# facetHound_inputs_mast_v13.net
KiCad netlist of a schematic drawn in EAGLE
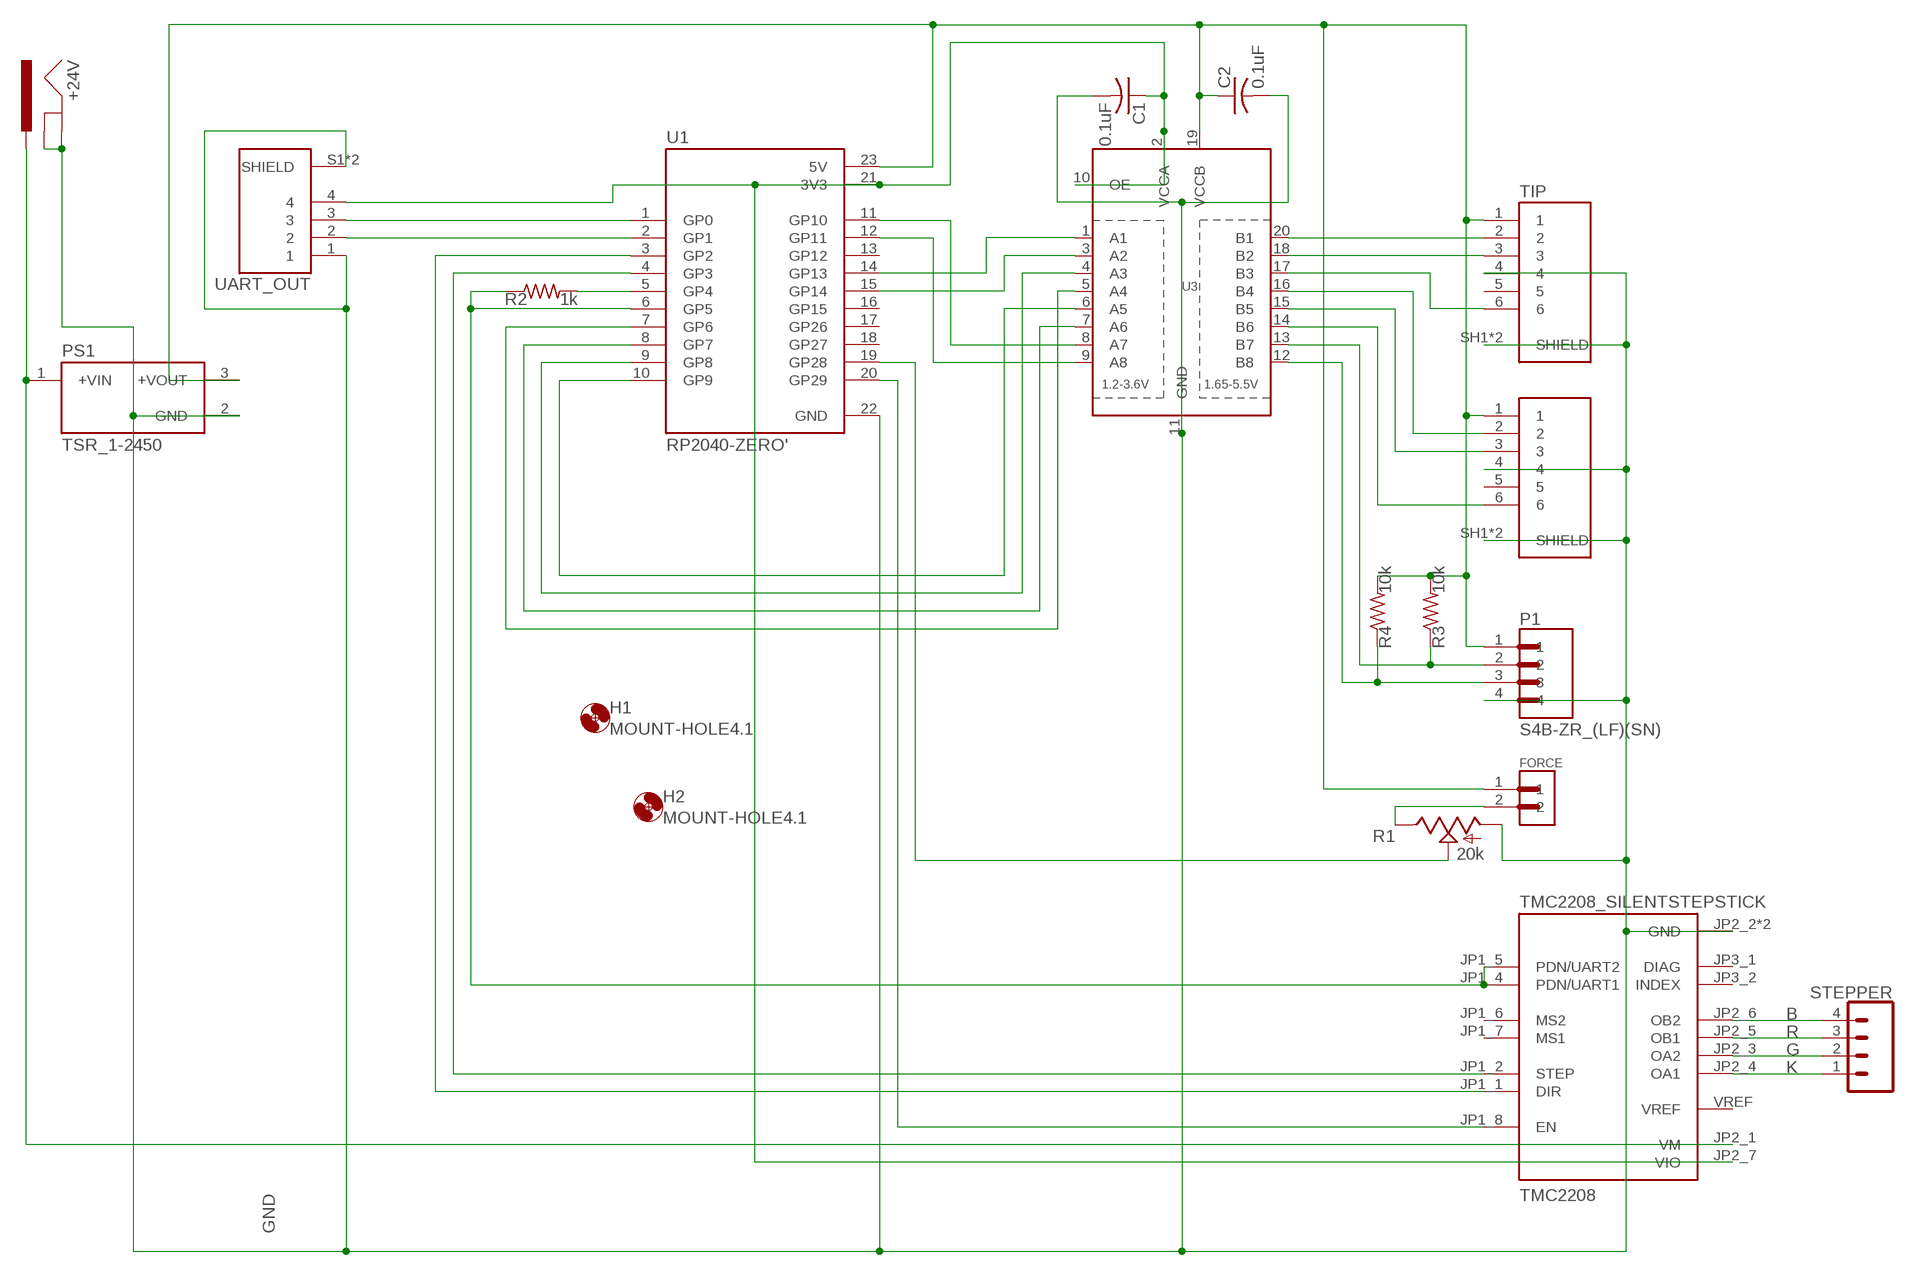
[diagram p0: schematic, sheet 1]

(export (version "E")
  (design (tool "Eeschema 10.0.6"))
  (components
    (comp (ref "+24V")
      (value "POWER_JACKPOWER_JACK_SLOT")
      (footprint "eagle-import:POWER_JACK_PTH_SLOT")
      (libsource (lib "eagle-import") (part "POWER_JACKPOWER_JACK_SLOT"))
    )
    (comp (ref "C1")
      (value "0.1uF")
      (footprint "eagle-import:C1206")
      (libsource (lib "eagle-import") (part "C-USC1206"))
    )
    (comp (ref "C2")
      (value "0.1uF")
      (footprint "eagle-import:C1206")
      (libsource (lib "eagle-import") (part "C-USC1206"))
    )
    (comp (ref "FORCE")
      (value "S2B-ZR-SM4A-TF")
      (footprint "eagle-import:JST_S2B-ZR-SM4A-TF")
      (fields (field (name "MF") "JST Sales"))
      (libsource (lib "eagle-import") (part "S2B-ZR-SM4A-TF"))
    )
    (comp (ref "H1")
      (value "MOUNT-HOLE4.1")
      (footprint "eagle-import:4,1")
      (libsource (lib "eagle-import") (part "MOUNT-HOLE4.1"))
    )
    (comp (ref "H2")
      (value "MOUNT-HOLE4.1")
      (footprint "eagle-import:4,1")
      (libsource (lib "eagle-import") (part "MOUNT-HOLE4.1"))
    )
    (comp (ref "P1")
      (value "S4B-ZR_(LF)(SN)")
      (footprint "eagle-import:JST_S4B-ZR(LF)(SN)")
      (fields (field (name "MF") "JST Sales") (field (name "MP") "S4B-ZR (LF)(SN)"))
      (libsource (lib "eagle-import") (part "S4B-ZR_(LF)(SN)"))
    )
    (comp (ref "PS1")
      (value "TSR_1-2450")
      (footprint "eagle-import:CONV_TSR_1-2450")
      (fields (field (name "MANUFACTURER") "Traco Power"))
      (libsource (lib "eagle-import") (part "TSR_1-2450"))
    )
    (comp (ref "R1")
      (value "20k")
      (footprint "eagle-import:RJ9W")
      (libsource (lib "eagle-import") (part "TRIM_US-RJ9W"))
    )
    (comp (ref "R2")
      (value "1k")
      (footprint "eagle-import:R1206")
      (libsource (lib "eagle-import") (part "R-US_R1206"))
    )
    (comp (ref "R3")
      (value "10k")
      (footprint "eagle-import:R1206")
      (libsource (lib "eagle-import") (part "R-US_R1206"))
    )
    (comp (ref "R4")
      (value "10k")
      (footprint "eagle-import:R1206")
      (libsource (lib "eagle-import") (part "R-US_R1206"))
    )
    (comp (ref "STEPPER")
      (value "CONN_04JST-PTH")
      (footprint "eagle-import:JST-4-PTH")
      (libsource (lib "eagle-import") (part "CONN_04JST-PTH"))
    )
    (comp (ref "TILT")
      (value "S6B-ZR-SM4A-TF(LF)(SN)")
      (footprint "eagle-import:JST_S6B-ZR-SM4A-TF(LF)(SN)")
      (fields (field (name "MF") "JST Sales America Inc."))
      (libsource (lib "eagle-import") (part "S6B-ZR-SM4A-TF(LF)(SN)"))
    )
    (comp (ref "TIP")
      (value "S6B-ZR-SM4A-TF(LF)(SN)")
      (footprint "eagle-import:JST_S6B-ZR-SM4A-TF(LF)(SN)")
      (fields (field (name "MF") "JST Sales America Inc."))
      (libsource (lib "eagle-import") (part "S6B-ZR-SM4A-TF(LF)(SN)"))
    )
    (comp (ref "TMC2208")
      (value "TMC2208_SILENTSTEPSTICK")
      (footprint "eagle-import:MODULE_TMC2208_SILENTSTEPSTICK")
      (fields (field (name "MF") "Trinamic Motion") (field (name "MP") "TMC2208 SILENTSTEPSTICK"))
      (libsource (lib "eagle-import") (part "TMC2208_SILENTSTEPSTICK"))
    )
    (comp (ref "U1")
      (value "RP2040-ZERO'")
      (footprint "eagle-import:MODULE_RP2040-ZERO")
      (fields (field (name "MF") "Waveshare Electronics") (field (name "MP") "RP2040-ZERO"))
      (libsource (lib "eagle-import") (part "RP2040-ZERO'"))
    )
    (comp (ref "U3")
      (value "TXB0108PWR")
      (footprint "eagle-import:TSSOP20")
      (libsource (lib "eagle-import") (part "TXB0108PWR"))
    )
    (comp (ref "UART_OUT")
      (value "S4B-ZR-SM4A-TF(LF)(SN)")
      (footprint "eagle-import:JST_S4B-ZR-SM4A-TF(LF)(SN)")
      (fields (field (name "MF") "JST Sales"))
      (libsource (lib "eagle-import") (part "S4B-ZR-SM4A-TF(LF)(SN)"))
    )
  )
  (nets
    (net (code "1") (name "B") (class "Default")
      (node (ref "STEPPER") (pin "4") (pinfunction "4_4") (pintype "passive"))
      (node (ref "TMC2208") (pin "JP2_6") (pinfunction "OB2_JP2_6") (pintype "passive"))
    )
    (net (code "2") (name "G") (class "Default")
      (node (ref "STEPPER") (pin "2") (pinfunction "2_2") (pintype "passive"))
      (node (ref "TMC2208") (pin "JP2_3") (pinfunction "OA2_JP2_3") (pintype "passive"))
    )
    (net (code "3") (name "GND") (class "Default")
      (node (ref "+24V") (pin "GND") (pinfunction "GND_GND") (pintype "bidirectional"))
      (node (ref "+24V") (pin "GNDBREAK") (pinfunction "GNDBREAK_GNDBREAK") (pintype "bidirectional"))
      (node (ref "C1") (pin "2") (pinfunction "2_2") (pintype "passive"))
      (node (ref "C2") (pin "2") (pinfunction "2_2") (pintype "passive"))
      (node (ref "P1") (pin "4") (pinfunction "4_4") (pintype "passive"))
      (node (ref "PS1") (pin "2") (pinfunction "GND_2") (pintype "power_in"))
      (node (ref "R1") (pin "A") (pinfunction "A_A") (pintype "passive"))
      (node (ref "TILT") (pin "4") (pinfunction "4_4") (pintype "passive"))
      (node (ref "TILT") (pin "SH1") (pinfunction "SHIELD_SH1") (pintype "passive"))
      (node (ref "TILT") (pin "SH2") (pinfunction "SHIELD_SH2") (pintype "passive"))
      (node (ref "TIP") (pin "4") (pinfunction "4_4") (pintype "passive"))
      (node (ref "TIP") (pin "SH1") (pinfunction "SHIELD_SH1") (pintype "passive"))
      (node (ref "TIP") (pin "SH2") (pinfunction "SHIELD_SH2") (pintype "passive"))
      (node (ref "TMC2208") (pin "JP2_2") (pinfunction "GND_JP2_2") (pintype "power_in"))
      (node (ref "TMC2208") (pin "JP2_8") (pinfunction "GND_JP2_8") (pintype "power_in"))
      (node (ref "U1") (pin "22") (pinfunction "GND_22") (pintype "power_in"))
      (node (ref "U3") (pin "11") (pinfunction "GND_11") (pintype "bidirectional"))
      (node (ref "UART_OUT") (pin "1") (pinfunction "1_1") (pintype "passive"))
      (node (ref "UART_OUT") (pin "S1") (pinfunction "SHIELD_S1") (pintype "passive"))
      (node (ref "UART_OUT") (pin "S2") (pinfunction "SHIELD_S2") (pintype "passive"))
    )
    (net (code "4") (name "K") (class "Default")
      (node (ref "STEPPER") (pin "1") (pinfunction "1_1") (pintype "passive"))
      (node (ref "TMC2208") (pin "JP2_4") (pinfunction "OA1_JP2_4") (pintype "passive"))
    )
    (net (code "5") (name "Net-(FORCE-Pad2)") (class "Default")
      (node (ref "FORCE") (pin "2") (pinfunction "2_2") (pintype "passive"))
      (node (ref "R1") (pin "E") (pinfunction "E_E") (pintype "passive"))
    )
    (net (code "6") (name "Net-(PS1-+VIN)") (class "Default")
      (node (ref "+24V") (pin "PWR") (pinfunction "PWR_PWR") (pintype "bidirectional"))
      (node (ref "PS1") (pin "1") (pinfunction "+VIN_1") (pintype "input"))
      (node (ref "TMC2208") (pin "JP2_1") (pinfunction "VM_JP2_1") (pintype "power_in"))
    )
    (net (code "7") (name "Net-(PS1-+VOUT)") (class "Default")
      (node (ref "C2") (pin "1") (pinfunction "1_1") (pintype "passive"))
      (node (ref "FORCE") (pin "1") (pinfunction "1_1") (pintype "passive"))
      (node (ref "P1") (pin "1") (pinfunction "1_1") (pintype "passive"))
      (node (ref "PS1") (pin "3") (pinfunction "+VOUT_3") (pintype "output"))
      (node (ref "R3") (pin "2") (pinfunction "2_2") (pintype "passive"))
      (node (ref "R4") (pin "2") (pinfunction "2_2") (pintype "passive"))
      (node (ref "TILT") (pin "1") (pinfunction "1_1") (pintype "passive"))
      (node (ref "TIP") (pin "1") (pinfunction "1_1") (pintype "passive"))
      (node (ref "U1") (pin "23") (pinfunction "5V_23") (pintype "power_in"))
      (node (ref "U3") (pin "19") (pinfunction "VCCB_19") (pintype "bidirectional"))
    )
    (net (code "8") (name "Net-(TMC2208-DIR)") (class "Default")
      (node (ref "TMC2208") (pin "JP1_1") (pinfunction "DIR_JP1_1") (pintype "input"))
      (node (ref "U1") (pin "3") (pinfunction "GP2_3") (pintype "bidirectional"))
    )
    (net (code "9") (name "Net-(TMC2208-EN)") (class "Default")
      (node (ref "TMC2208") (pin "JP1_8") (pinfunction "EN_JP1_8") (pintype "input"))
      (node (ref "U1") (pin "20") (pinfunction "GP29_20") (pintype "bidirectional"))
    )
    (net (code "10") (name "Net-(TMC2208-PDN{slash}UART1)") (class "Default")
      (node (ref "R2") (pin "1") (pinfunction "1_1") (pintype "passive"))
      (node (ref "TMC2208") (pin "JP1_4") (pinfunction "PDN/UART1_JP1_4") (pintype "bidirectional"))
      (node (ref "TMC2208") (pin "JP1_5") (pinfunction "PDN/UART2_JP1_5") (pintype "bidirectional"))
      (node (ref "U1") (pin "6") (pinfunction "GP5_6") (pintype "bidirectional"))
    )
    (net (code "11") (name "Net-(TMC2208-STEP)") (class "Default")
      (node (ref "TMC2208") (pin "JP1_2") (pinfunction "STEP_JP1_2") (pintype "input"))
      (node (ref "U1") (pin "4") (pinfunction "GP3_4") (pintype "bidirectional"))
    )
    (net (code "12") (name "Net-(TMC2208-VIO)") (class "Default")
      (node (ref "C1") (pin "1") (pinfunction "1_1") (pintype "passive"))
      (node (ref "TMC2208") (pin "JP2_7") (pinfunction "VIO_JP2_7") (pintype "power_in"))
      (node (ref "U1") (pin "21") (pinfunction "3V3_21") (pintype "power_in"))
      (node (ref "U3") (pin "10") (pinfunction "OE_10") (pintype "bidirectional"))
      (node (ref "U3") (pin "2") (pinfunction "VCCA_2") (pintype "bidirectional"))
      (node (ref "UART_OUT") (pin "4") (pinfunction "4_4") (pintype "passive"))
    )
    (net (code "13") (name "Net-(U1-GP0)") (class "Default")
      (node (ref "U1") (pin "1") (pinfunction "GP0_1") (pintype "bidirectional"))
      (node (ref "UART_OUT") (pin "3") (pinfunction "3_3") (pintype "passive"))
    )
    (net (code "14") (name "Net-(U1-GP1)") (class "Default")
      (node (ref "U1") (pin "2") (pinfunction "GP1_2") (pintype "bidirectional"))
      (node (ref "UART_OUT") (pin "2") (pinfunction "2_2") (pintype "passive"))
    )
    (net (code "15") (name "Net-(U1-GP4)") (class "Default")
      (node (ref "R2") (pin "2") (pinfunction "2_2") (pintype "passive"))
      (node (ref "U1") (pin "5") (pinfunction "GP4_5") (pintype "bidirectional"))
    )
    (net (code "16") (name "Net-(U1-GP6)") (class "Default")
      (node (ref "U1") (pin "7") (pinfunction "GP6_7") (pintype "bidirectional"))
      (node (ref "U3") (pin "5") (pinfunction "A4_5") (pintype "bidirectional"))
    )
    (net (code "17") (name "Net-(U1-GP7)") (class "Default")
      (node (ref "U1") (pin "8") (pinfunction "GP7_8") (pintype "bidirectional"))
      (node (ref "U3") (pin "7") (pinfunction "A6_7") (pintype "bidirectional"))
    )
    (net (code "18") (name "Net-(U1-GP8)") (class "Default")
      (node (ref "U1") (pin "9") (pinfunction "GP8_9") (pintype "bidirectional"))
      (node (ref "U3") (pin "4") (pinfunction "A3_4") (pintype "bidirectional"))
    )
    (net (code "19") (name "Net-(U1-GP9)") (class "Default")
      (node (ref "U1") (pin "10") (pinfunction "GP9_10") (pintype "bidirectional"))
      (node (ref "U3") (pin "6") (pinfunction "A5_6") (pintype "bidirectional"))
    )
    (net (code "20") (name "Net-(U1-GP10)") (class "Default")
      (node (ref "U1") (pin "11") (pinfunction "GP10_11") (pintype "bidirectional"))
      (node (ref "U3") (pin "8") (pinfunction "A7_8") (pintype "bidirectional"))
    )
    (net (code "21") (name "Net-(U1-GP11)") (class "Default")
      (node (ref "U1") (pin "12") (pinfunction "GP11_12") (pintype "bidirectional"))
      (node (ref "U3") (pin "9") (pinfunction "A8_9") (pintype "bidirectional"))
    )
    (net (code "22") (name "Net-(U1-GP13)") (class "Default")
      (node (ref "U1") (pin "14") (pinfunction "GP13_14") (pintype "bidirectional"))
      (node (ref "U3") (pin "1") (pinfunction "A1_1") (pintype "bidirectional"))
    )
    (net (code "23") (name "Net-(U1-GP14)") (class "Default")
      (node (ref "U1") (pin "15") (pinfunction "GP14_15") (pintype "bidirectional"))
      (node (ref "U3") (pin "3") (pinfunction "A2_3") (pintype "bidirectional"))
    )
    (net (code "24") (name "Net-(U1-GP28)") (class "Default")
      (node (ref "R1") (pin "S") (pinfunction "S_S") (pintype "passive"))
      (node (ref "U1") (pin "19") (pinfunction "GP28_19") (pintype "bidirectional"))
    )
    (net (code "25") (name "Net-(U3-B1)") (class "Default")
      (node (ref "TIP") (pin "2") (pinfunction "2_2") (pintype "passive"))
      (node (ref "U3") (pin "20") (pinfunction "B1_20") (pintype "bidirectional"))
    )
    (net (code "26") (name "Net-(U3-B2)") (class "Default")
      (node (ref "TIP") (pin "3") (pinfunction "3_3") (pintype "passive"))
      (node (ref "U3") (pin "18") (pinfunction "B2_18") (pintype "bidirectional"))
    )
    (net (code "27") (name "Net-(U3-B3)") (class "Default")
      (node (ref "TIP") (pin "6") (pinfunction "6_6") (pintype "passive"))
      (node (ref "U3") (pin "17") (pinfunction "B3_17") (pintype "bidirectional"))
    )
    (net (code "28") (name "Net-(U3-B4)") (class "Default")
      (node (ref "TILT") (pin "2") (pinfunction "2_2") (pintype "passive"))
      (node (ref "U3") (pin "16") (pinfunction "B4_16") (pintype "bidirectional"))
    )
    (net (code "29") (name "Net-(U3-B5)") (class "Default")
      (node (ref "TILT") (pin "3") (pinfunction "3_3") (pintype "passive"))
      (node (ref "U3") (pin "15") (pinfunction "B5_15") (pintype "bidirectional"))
    )
    (net (code "30") (name "Net-(U3-B6)") (class "Default")
      (node (ref "TILT") (pin "6") (pinfunction "6_6") (pintype "passive"))
      (node (ref "U3") (pin "14") (pinfunction "B6_14") (pintype "bidirectional"))
    )
    (net (code "31") (name "Net-(U3-B7)") (class "Default")
      (node (ref "P1") (pin "2") (pinfunction "2_2") (pintype "passive"))
      (node (ref "R3") (pin "1") (pinfunction "1_1") (pintype "passive"))
      (node (ref "U3") (pin "13") (pinfunction "B7_13") (pintype "bidirectional"))
    )
    (net (code "32") (name "Net-(U3-B8)") (class "Default")
      (node (ref "P1") (pin "3") (pinfunction "3_3") (pintype "passive"))
      (node (ref "R4") (pin "1") (pinfunction "1_1") (pintype "passive"))
      (node (ref "U3") (pin "12") (pinfunction "B8_12") (pintype "bidirectional"))
    )
    (net (code "33") (name "R") (class "Default")
      (node (ref "STEPPER") (pin "3") (pinfunction "3_3") (pintype "passive"))
      (node (ref "TMC2208") (pin "JP2_5") (pinfunction "OB1_JP2_5") (pintype "passive"))
    )
    (net (code "34") (name "unconnected-(TILT-Pad5)") (class "Default")
      (node (ref "TILT") (pin "5") (pinfunction "5_5") (pintype "passive"))
    )
    (net (code "35") (name "unconnected-(TIP-Pad5)") (class "Default")
      (node (ref "TIP") (pin "5") (pinfunction "5_5") (pintype "passive"))
    )
    (net (code "36") (name "unconnected-(TMC2208-DIAG-PadJP3_1)") (class "Default")
      (node (ref "TMC2208") (pin "JP3_1") (pinfunction "DIAG_JP3_1") (pintype "output"))
    )
    (net (code "37") (name "unconnected-(TMC2208-INDEX-PadJP3_2)") (class "Default")
      (node (ref "TMC2208") (pin "JP3_2") (pinfunction "INDEX_JP3_2") (pintype "output"))
    )
    (net (code "38") (name "unconnected-(TMC2208-MS1-PadJP1_7)") (class "Default")
      (node (ref "TMC2208") (pin "JP1_7") (pinfunction "MS1_JP1_7") (pintype "input"))
    )
    (net (code "39") (name "unconnected-(TMC2208-MS2-PadJP1_6)") (class "Default")
      (node (ref "TMC2208") (pin "JP1_6") (pinfunction "MS2_JP1_6") (pintype "input"))
    )
    (net (code "40") (name "unconnected-(TMC2208-PadVREF)") (class "Default")
      (node (ref "TMC2208") (pin "VREF") (pinfunction "VREF_VREF") (pintype "passive"))
    )
    (net (code "41") (name "unconnected-(U1-GP12-Pad13)") (class "Default")
      (node (ref "U1") (pin "13") (pinfunction "GP12_13") (pintype "bidirectional"))
    )
    (net (code "42") (name "unconnected-(U1-GP15-Pad16)") (class "Default")
      (node (ref "U1") (pin "16") (pinfunction "GP15_16") (pintype "bidirectional"))
    )
    (net (code "43") (name "unconnected-(U1-GP26-Pad17)") (class "Default")
      (node (ref "U1") (pin "17") (pinfunction "GP26_17") (pintype "bidirectional"))
    )
    (net (code "44") (name "unconnected-(U1-GP27-Pad18)") (class "Default")
      (node (ref "U1") (pin "18") (pinfunction "GP27_18") (pintype "bidirectional"))
    )
  )
)
